# udemy_course.net
KiCad netlist of a schematic drawn in EAGLE
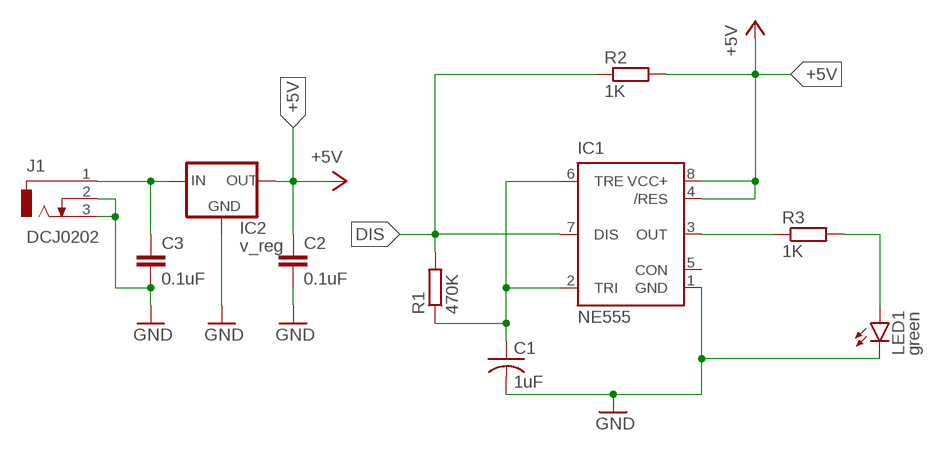
[diagram p0: schematic, sheet 1]

(export (version "E")
  (design (tool "Eeschema 10.0.6"))
  (components
    (comp (ref "C1")
      (value "1uF")
      (footprint "eagle-import:C050-045X075")
      (libsource (lib "eagle-import") (part "C-US050-045X075"))
    )
    (comp (ref "C2")
      (value "0.1uF")
      (footprint "eagle-import:C025-050X050")
      (libsource (lib "eagle-import") (part "C-EU025-050X050"))
    )
    (comp (ref "C3")
      (value "0.1uF")
      (footprint "eagle-import:C025-050X050")
      (libsource (lib "eagle-import") (part "C-EU025-050X050"))
    )
    (comp (ref "IC1")
      (value "NE555")
      (footprint "eagle-import:DIL-08")
      (fields (field (name "MF") "Arrow Electronics") (field (name "MPN") "NE555N"))
      (libsource (lib "eagle-import") (part "NE555"))
    )
    (comp (ref "IC2")
      (value "v_reg")
      (footprint "eagle-import:78XXS")
      (libsource (lib "eagle-import") (part "78XXS"))
    )
    (comp (ref "J1")
      (value "DCJ0202")
      (footprint "eagle-import:DCJ0202")
      (libsource (lib "eagle-import") (part "DCJ0202"))
    )
    (comp (ref "LED1")
      (value "green")
      (footprint "eagle-import:LED5MM")
      (libsource (lib "eagle-import") (part "LED5MM"))
    )
    (comp (ref "R1")
      (value "470K")
      (footprint "eagle-import:0411_15")
      (libsource (lib "eagle-import") (part "R-EU_0411/15"))
    )
    (comp (ref "R2")
      (value "1K")
      (footprint "eagle-import:0411_15")
      (libsource (lib "eagle-import") (part "R-EU_0411/15"))
    )
    (comp (ref "R3")
      (value "1K")
      (footprint "eagle-import:0411_15")
      (libsource (lib "eagle-import") (part "R-EU_0411/15"))
    )
  )
  (nets
    (net (code "1") (name "+5V") (class "Default")
      (node (ref "C2") (pin "1") (pinfunction "1_1") (pintype "passive"))
      (node (ref "IC1") (pin "4") (pinfunction "/RES_4") (pintype "input"))
      (node (ref "IC1") (pin "8") (pinfunction "VCC+_8") (pintype "power_in"))
      (node (ref "IC2") (pin "OUT") (pinfunction "OUT_OUT") (pintype "passive"))
      (node (ref "R2") (pin "2") (pinfunction "2_2") (pintype "passive"))
    )
    (net (code "2") (name "DIS") (class "Default")
      (node (ref "IC1") (pin "7") (pinfunction "DIS_7") (pintype "input"))
      (node (ref "R1") (pin "2") (pinfunction "2_2") (pintype "passive"))
      (node (ref "R2") (pin "1") (pinfunction "1_1") (pintype "passive"))
    )
    (net (code "3") (name "GND") (class "Default")
      (node (ref "C1") (pin "2") (pinfunction "2_2") (pintype "passive"))
      (node (ref "C2") (pin "2") (pinfunction "2_2") (pintype "passive"))
      (node (ref "C3") (pin "2") (pinfunction "2_2") (pintype "passive"))
      (node (ref "IC1") (pin "1") (pinfunction "GND_1") (pintype "power_in"))
      (node (ref "IC2") (pin "GND") (pinfunction "GND_GND") (pintype "input"))
      (node (ref "J1") (pin "2") (pinfunction "2_2") (pintype "passive"))
      (node (ref "J1") (pin "3") (pinfunction "3_3") (pintype "passive"))
      (node (ref "LED1") (pin "K") (pinfunction "C_K") (pintype "passive"))
    )
    (net (code "4") (name "Net-(C3-Pad1)") (class "Default")
      (node (ref "C3") (pin "1") (pinfunction "1_1") (pintype "passive"))
      (node (ref "IC2") (pin "IN") (pinfunction "IN_IN") (pintype "input"))
      (node (ref "J1") (pin "1") (pinfunction "1_1") (pintype "passive"))
    )
    (net (code "5") (name "Net-(IC1-OUT)") (class "Default")
      (node (ref "IC1") (pin "3") (pinfunction "OUT_3") (pintype "output"))
      (node (ref "R3") (pin "1") (pinfunction "1_1") (pintype "passive"))
    )
    (net (code "6") (name "Net-(IC1-TRE)") (class "Default")
      (node (ref "C1") (pin "1") (pinfunction "1_1") (pintype "passive"))
      (node (ref "IC1") (pin "2") (pinfunction "TRI_2") (pintype "input"))
      (node (ref "IC1") (pin "6") (pinfunction "TRE_6") (pintype "input"))
      (node (ref "R1") (pin "1") (pinfunction "1_1") (pintype "passive"))
    )
    (net (code "7") (name "Net-(LED1-PadA)") (class "Default")
      (node (ref "LED1") (pin "A") (pinfunction "A_A") (pintype "passive"))
      (node (ref "R3") (pin "2") (pinfunction "2_2") (pintype "passive"))
    )
    (net (code "8") (name "unconnected-(IC1-CON-Pad5)") (class "Default")
      (node (ref "IC1") (pin "5") (pinfunction "CON_5") (pintype "input"))
    )
  )
)
